# Simplified_4_ch_sample-and-hold_without_.net
KiCad netlist of a schematic drawn in EAGLE
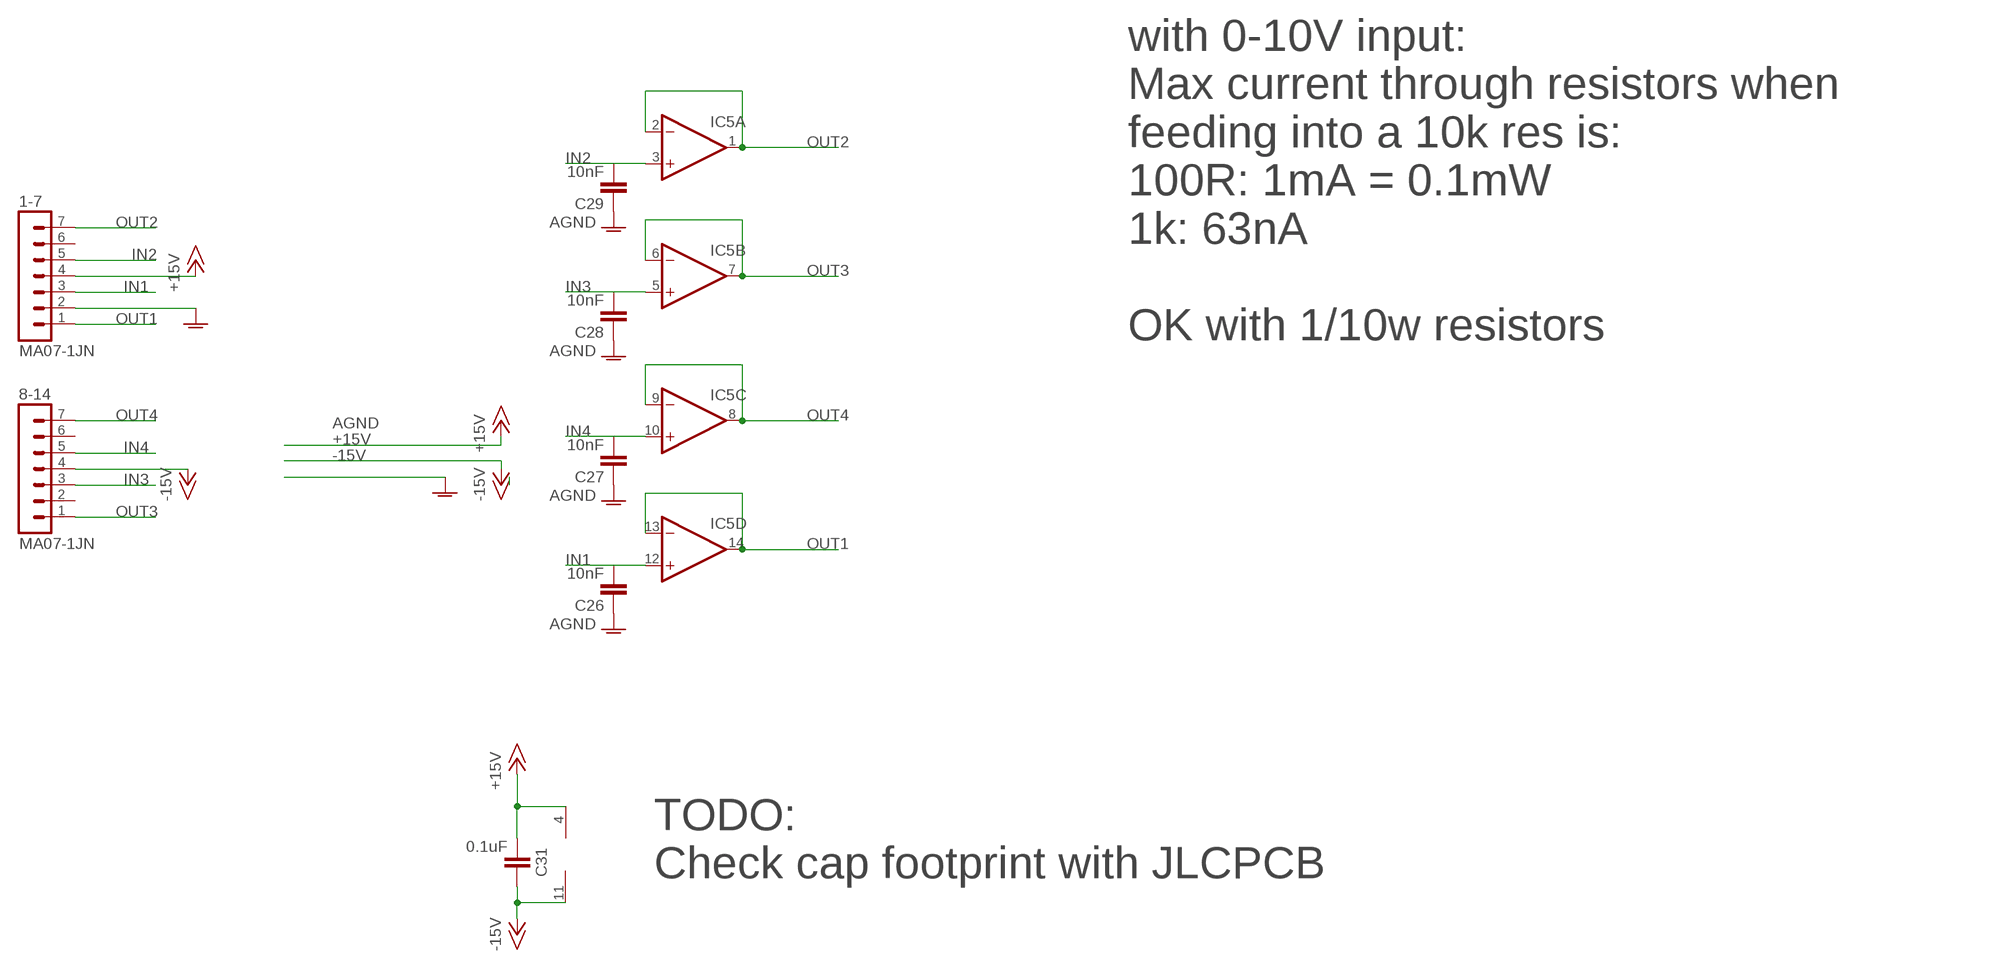
[diagram p0: schematic, sheet 1]

(export (version "E")
  (design (tool "Eeschema 10.0.6"))
  (components
    (comp (ref "1-7")
      (value "MA07-1JN")
      (footprint "eagle-import:MA07N-1J")
      (libsource (lib "eagle-import") (part "MA07-1JN"))
    )
    (comp (ref "8-14")
      (value "MA07-1JN")
      (footprint "eagle-import:MA07N-1J")
      (libsource (lib "eagle-import") (part "MA07-1JN"))
    )
    (comp (ref "C26")
      (value "10nF")
      (footprint "eagle-import:C0805")
      (libsource (lib "eagle-import") (part "C-EUC0805"))
    )
    (comp (ref "C27")
      (value "10nF")
      (footprint "eagle-import:C0805")
      (libsource (lib "eagle-import") (part "C-EUC0805"))
    )
    (comp (ref "C28")
      (value "10nF")
      (footprint "eagle-import:C0805")
      (libsource (lib "eagle-import") (part "C-EUC0805"))
    )
    (comp (ref "C29")
      (value "10nF")
      (footprint "eagle-import:C0805")
      (libsource (lib "eagle-import") (part "C-EUC0805"))
    )
    (comp (ref "C31")
      (value "0.1uF")
      (footprint "eagle-import:C0603")
      (libsource (lib "eagle-import") (part "resistor_C-EUC0603"))
    )
    (comp (ref "IC5")
      (value "TL084CPWR")
      (footprint "eagle-import:TSSOP14J")
      (libsource (lib "eagle-import") (part "TL074JT"))
    )
  )
  (nets
    (net (code "1") (name "+15V") (class "Default")
      (node (ref "1-7") (pin "4") (pinfunction "4_4") (pintype "passive"))
      (node (ref "C31") (pin "1") (pinfunction "1_1") (pintype "passive"))
      (node (ref "IC5") (pin "4") (pinfunction "V+_4") (pintype "power_in"))
    )
    (net (code "2") (name "-15V") (class "Default")
      (node (ref "8-14") (pin "4") (pinfunction "4_4") (pintype "passive"))
      (node (ref "C31") (pin "2") (pinfunction "2_2") (pintype "passive"))
      (node (ref "IC5") (pin "11") (pinfunction "V-_11") (pintype "power_in"))
    )
    (net (code "3") (name "/IN1") (class "Default")
      (node (ref "1-7") (pin "3") (pinfunction "3_3") (pintype "passive"))
      (node (ref "C26") (pin "2") (pinfunction "2_2") (pintype "passive"))
      (node (ref "IC5") (pin "12") (pinfunction "+IN_12") (pintype "input"))
    )
    (net (code "4") (name "/IN2") (class "Default")
      (node (ref "1-7") (pin "5") (pinfunction "5_5") (pintype "passive"))
      (node (ref "C29") (pin "2") (pinfunction "2_2") (pintype "passive"))
      (node (ref "IC5") (pin "3") (pinfunction "+IN_3") (pintype "input"))
    )
    (net (code "5") (name "/IN3") (class "Default")
      (node (ref "8-14") (pin "3") (pinfunction "3_3") (pintype "passive"))
      (node (ref "C28") (pin "2") (pinfunction "2_2") (pintype "passive"))
      (node (ref "IC5") (pin "5") (pinfunction "+IN_5") (pintype "input"))
    )
    (net (code "6") (name "/IN4") (class "Default")
      (node (ref "8-14") (pin "5") (pinfunction "5_5") (pintype "passive"))
      (node (ref "C27") (pin "2") (pinfunction "2_2") (pintype "passive"))
      (node (ref "IC5") (pin "10") (pinfunction "+IN_10") (pintype "input"))
    )
    (net (code "7") (name "/OUT1") (class "Default")
      (node (ref "1-7") (pin "1") (pinfunction "1_1") (pintype "passive"))
      (node (ref "IC5") (pin "13") (pinfunction "-IN_13") (pintype "input"))
      (node (ref "IC5") (pin "14") (pinfunction "OUT_14") (pintype "output"))
    )
    (net (code "8") (name "/OUT2") (class "Default")
      (node (ref "1-7") (pin "7") (pinfunction "7_7") (pintype "passive"))
      (node (ref "IC5") (pin "1") (pinfunction "OUT_1") (pintype "output"))
      (node (ref "IC5") (pin "2") (pinfunction "-IN_2") (pintype "input"))
    )
    (net (code "9") (name "/OUT3") (class "Default")
      (node (ref "8-14") (pin "1") (pinfunction "1_1") (pintype "passive"))
      (node (ref "IC5") (pin "6") (pinfunction "-IN_6") (pintype "input"))
      (node (ref "IC5") (pin "7") (pinfunction "OUT_7") (pintype "output"))
    )
    (net (code "10") (name "/OUT4") (class "Default")
      (node (ref "8-14") (pin "7") (pinfunction "7_7") (pintype "passive"))
      (node (ref "IC5") (pin "8") (pinfunction "OUT_8") (pintype "output"))
      (node (ref "IC5") (pin "9") (pinfunction "-IN_9") (pintype "input"))
    )
    (net (code "11") (name "AGND") (class "Default")
      (node (ref "1-7") (pin "2") (pinfunction "2_2") (pintype "passive"))
      (node (ref "C26") (pin "1") (pinfunction "1_1") (pintype "passive"))
      (node (ref "C27") (pin "1") (pinfunction "1_1") (pintype "passive"))
      (node (ref "C28") (pin "1") (pinfunction "1_1") (pintype "passive"))
      (node (ref "C29") (pin "1") (pinfunction "1_1") (pintype "passive"))
    )
    (net (code "12") (name "unconnected-(1-7-Pad6)") (class "Default")
      (node (ref "1-7") (pin "6") (pinfunction "6_6") (pintype "passive"))
    )
    (net (code "13") (name "unconnected-(8-14-Pad2)") (class "Default")
      (node (ref "8-14") (pin "2") (pinfunction "2_2") (pintype "passive"))
    )
    (net (code "14") (name "unconnected-(8-14-Pad6)") (class "Default")
      (node (ref "8-14") (pin "6") (pinfunction "6_6") (pintype "passive"))
    )
  )
)
